# mw_itb_half_v1_7_2.net
KiCad netlist of a schematic drawn in EAGLE
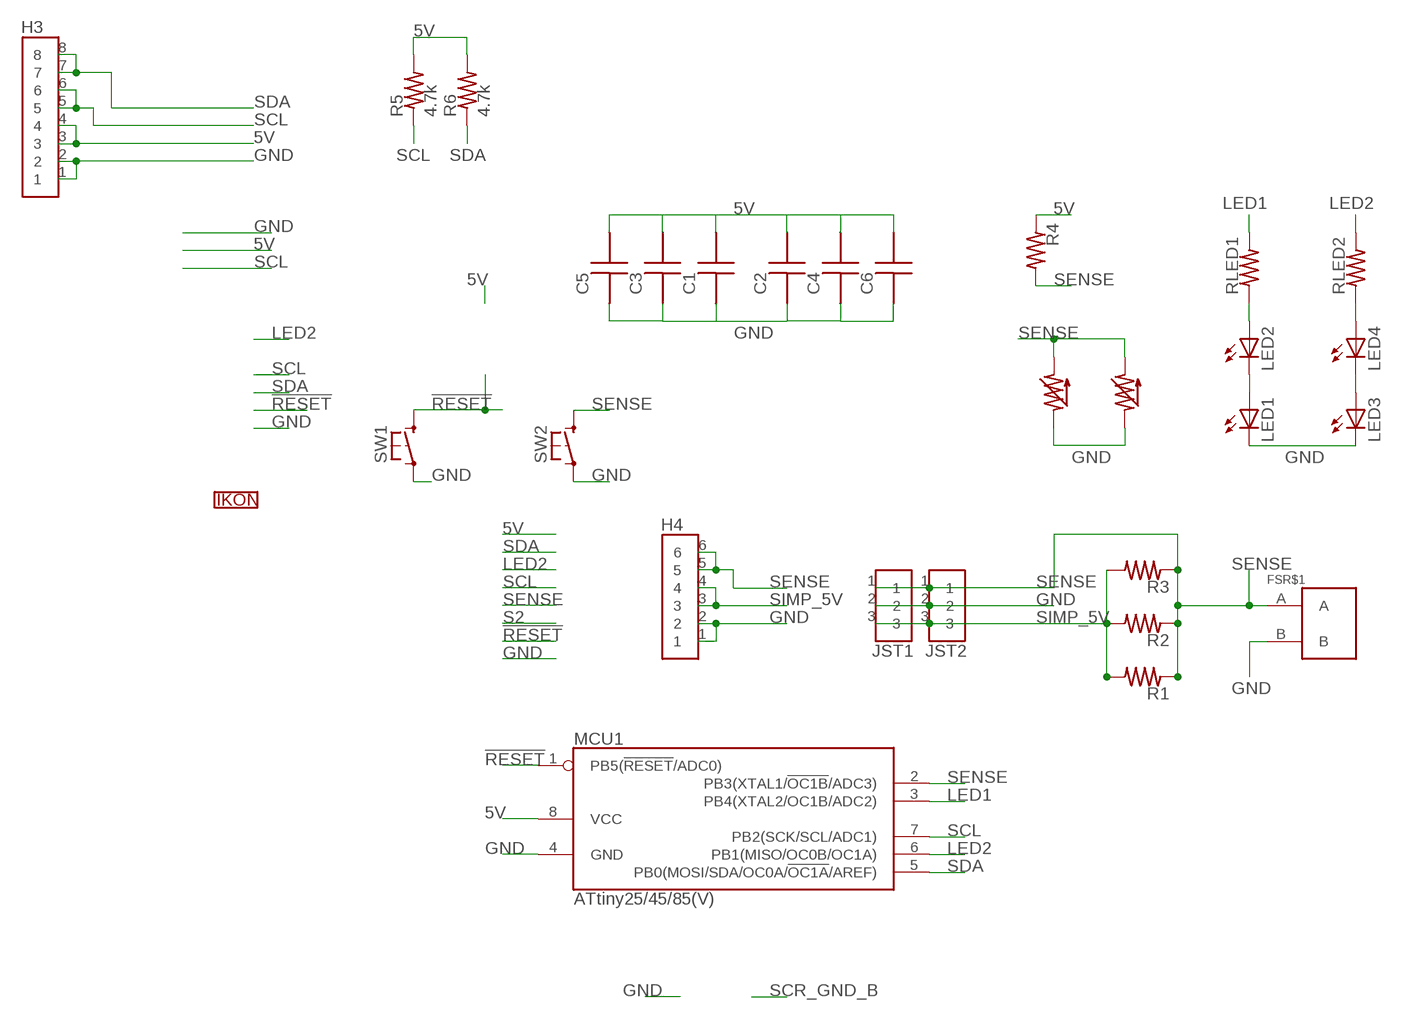
[diagram p0: schematic, sheet 1]

(export (version "E")
  (design (tool "Eeschema 10.0.6"))
  (components
    (comp (ref "C1")
      (value "CAPACITOR1206")
      (footprint "eagle-import:1206_YAGEO")
      (libsource (lib "eagle-import") (part "CAPACITOR1206"))
    )
    (comp (ref "C2")
      (value "CAPACITOR1206")
      (footprint "eagle-import:1206_YAGEO")
      (libsource (lib "eagle-import") (part "CAPACITOR1206"))
    )
    (comp (ref "C3")
      (value "CAPACITOR0805")
      (footprint "eagle-import:0805_YAGEO")
      (libsource (lib "eagle-import") (part "CAPACITOR0805"))
    )
    (comp (ref "C4")
      (value "CAPACITOR0805")
      (footprint "eagle-import:0805_YAGEO")
      (libsource (lib "eagle-import") (part "CAPACITOR0805"))
    )
    (comp (ref "C5")
      (value "CAPACITOR0603")
      (footprint "eagle-import:0603_YAGEO")
      (libsource (lib "eagle-import") (part "CAPACITOR0603"))
    )
    (comp (ref "C6")
      (value "CAPACITOR0603")
      (footprint "eagle-import:0603_YAGEO")
      (libsource (lib "eagle-import") (part "CAPACITOR0603"))
    )
    (comp (ref "FSR$1")
      (value "FSR_PAD88X44_P2B")
      (footprint "eagle-import:FSR_PAD_88X44_P2B")
      (libsource (lib "eagle-import") (part "FSR_PAD88X44_P2B"))
    )
    (comp (ref "H3")
      (value "HEADER_8P-0.1\"_2X4-SMD-SULLINS")
      (footprint "eagle-import:HEADER-0.1__2X4-SMD-SULLINS")
      (libsource (lib "eagle-import") (part "HEADER_8P-0.1{dblquote}_2X4-SMD-SULLINS"))
    )
    (comp (ref "H4")
      (value "HEADER_6P-0.1\"_2X3-SMD-SULLINS")
      (footprint "eagle-import:HEADER-0.1__2X3-SMD-SULLINS")
      (libsource (lib "eagle-import") (part "HEADER_6P-0.1{dblquote}_2X3-SMD-SULLINS"))
    )
    (comp (ref "JST1")
      (value "JST-3-PH-SMD-TOP")
      (footprint "eagle-import:JST_PH_SMD_3_TOP")
      (libsource (lib "eagle-import") (part "JST-3-PH-SMD-TOP"))
    )
    (comp (ref "JST2")
      (value "JST-3-PH-SMD-TOP")
      (footprint "eagle-import:JST_PH_SMD_3_TOP")
      (libsource (lib "eagle-import") (part "JST-3-PH-SMD-TOP"))
    )
    (comp (ref "LED1")
      (value "LED-ZBEND_RM")
      (footprint "eagle-import:Z-BEND_RM")
      (libsource (lib "eagle-import") (part "LED-ZBEND_RM"))
    )
    (comp (ref "LED2")
      (value "LED-ZBEND_RM")
      (footprint "eagle-import:Z-BEND_RM")
      (libsource (lib "eagle-import") (part "LED-ZBEND_RM"))
    )
    (comp (ref "LED3")
      (value "LED-ZBEND_RM")
      (footprint "eagle-import:Z-BEND_RM")
      (libsource (lib "eagle-import") (part "LED-ZBEND_RM"))
    )
    (comp (ref "LED4")
      (value "LED-ZBEND_RM")
      (footprint "eagle-import:Z-BEND_RM")
      (libsource (lib "eagle-import") (part "LED-ZBEND_RM"))
    )
    (comp (ref "MCU1")
      (value "ATMEL_ATTINY25/45/85(V)-SOIC_DUAL")
      (footprint "eagle-import:SOIC-8_DUAL")
      (libsource (lib "eagle-import") (part "ATMEL_ATTINY25/45/85(V)-SOIC_DUAL"))
    )
    (comp (ref "R1")
      (value "RESISTOR1206")
      (footprint "eagle-import:1206_YAGEO")
      (libsource (lib "eagle-import") (part "RESISTOR1206"))
    )
    (comp (ref "R2")
      (value "RESISTOR0805")
      (footprint "eagle-import:0805_YAGEO")
      (libsource (lib "eagle-import") (part "RESISTOR0805"))
    )
    (comp (ref "R3")
      (value "RESISTOR0603")
      (footprint "eagle-import:0603_YAGEO")
      (libsource (lib "eagle-import") (part "RESISTOR0603"))
    )
    (comp (ref "R4")
      (value "RESISTOR0603")
      (footprint "eagle-import:0603_YAGEO")
      (libsource (lib "eagle-import") (part "RESISTOR0603"))
    )
    (comp (ref "R5")
      (value "4.7k")
      (footprint "eagle-import:0603_YAGEO")
      (libsource (lib "eagle-import") (part "RESISTOR0603"))
    )
    (comp (ref "R6")
      (value "4.7k")
      (footprint "eagle-import:0603_YAGEO")
      (libsource (lib "eagle-import") (part "RESISTOR0603"))
    )
    (comp (ref "RLED1")
      (value "RESISTOR0603")
      (footprint "eagle-import:0603_YAGEO")
      (libsource (lib "eagle-import") (part "RESISTOR0603"))
    )
    (comp (ref "RLED2")
      (value "RESISTOR0603")
      (footprint "eagle-import:0603_YAGEO")
      (libsource (lib "eagle-import") (part "RESISTOR0603"))
    )
    (comp (ref "SW1")
      (value "SWITCH_SPST-KMT0")
      (footprint "eagle-import:KMT0")
      (libsource (lib "eagle-import") (part "SWITCH_SPST-KMT0"))
    )
    (comp (ref "SW2")
      (value "SWITCH_SPST-KMT0")
      (footprint "eagle-import:KMT0")
      (libsource (lib "eagle-import") (part "SWITCH_SPST-KMT0"))
    )
    (comp (ref "U$5")
      (value "FSR_PLACE")
      (footprint "eagle-import:FSR_1.5[IN]_SQR")
      (libsource (lib "eagle-import") (part "FSR_PLACE1.5{dblquote}SQR"))
    )
    (comp (ref "U$6")
      (value "FSR_PLACE")
      (footprint "eagle-import:FSR_1.5[IN]_SQR")
      (libsource (lib "eagle-import") (part "FSR_PLACE1.5{dblquote}SQR"))
    )
    (comp (ref "U$9")
      (value "FSR_PINS")
      (footprint "eagle-import:FSR_0.1_-PITCH_PADS-0.05_X0.5_")
      (libsource (lib "eagle-import") (part "FSR_PINSJUMBO_SMD"))
    )
    (comp (ref "U$10")
      (value "FSR_PINS")
      (footprint "eagle-import:FSR_0.1_-PITCH_PADS-0.05_X0.5_")
      (libsource (lib "eagle-import") (part "FSR_PINSJUMBO_SMD"))
    )
    (comp (ref "U$11")
      (value "IKONLEARNING-20MIL")
      (footprint "eagle-import:IKON_LEARNING_20MIL")
      (libsource (lib "eagle-import") (part "IKONLEARNING-20MIL"))
    )
  )
  (nets
    (net (code "1") (name "/5V") (class "Default")
      (node (ref "C1") (pin "1") (pinfunction "P$1_1") (pintype "passive"))
      (node (ref "C2") (pin "1") (pinfunction "P$1_1") (pintype "passive"))
      (node (ref "C3") (pin "1") (pinfunction "P$1_1") (pintype "passive"))
      (node (ref "C4") (pin "1") (pinfunction "P$1_1") (pintype "passive"))
      (node (ref "C5") (pin "1") (pinfunction "P$1_1") (pintype "passive"))
      (node (ref "C6") (pin "1") (pinfunction "P$1_1") (pintype "passive"))
      (node (ref "H3") (pin "3") (pinfunction "3_3") (pintype "bidirectional"))
      (node (ref "H3") (pin "4") (pinfunction "4_4") (pintype "bidirectional"))
      (node (ref "MCU1") (pin "8") (pinfunction "VCC_8") (pintype "bidirectional"))
      (node (ref "R4") (pin "1") (pinfunction "1_1") (pintype "passive"))
      (node (ref "R5") (pin "2") (pinfunction "2_2") (pintype "passive"))
      (node (ref "R6") (pin "2") (pinfunction "2_2") (pintype "passive"))
    )
    (net (code "2") (name "/GND") (class "Default")
      (node (ref "C1") (pin "2") (pinfunction "P$2_2") (pintype "passive"))
      (node (ref "C2") (pin "2") (pinfunction "P$2_2") (pintype "passive"))
      (node (ref "C3") (pin "2") (pinfunction "P$2_2") (pintype "passive"))
      (node (ref "C4") (pin "2") (pinfunction "P$2_2") (pintype "passive"))
      (node (ref "C5") (pin "2") (pinfunction "P$2_2") (pintype "passive"))
      (node (ref "C6") (pin "2") (pinfunction "P$2_2") (pintype "passive"))
      (node (ref "FSR$1") (pin "B") (pinfunction "B_B") (pintype "bidirectional"))
      (node (ref "H3") (pin "1") (pinfunction "1_1") (pintype "bidirectional"))
      (node (ref "H3") (pin "2") (pinfunction "2_2") (pintype "bidirectional"))
      (node (ref "H4") (pin "1") (pinfunction "1_1") (pintype "bidirectional"))
      (node (ref "H4") (pin "2") (pinfunction "2_2") (pintype "bidirectional"))
      (node (ref "JST1") (pin "2") (pinfunction "2_2") (pintype "bidirectional"))
      (node (ref "JST2") (pin "2") (pinfunction "2_2") (pintype "bidirectional"))
      (node (ref "LED1") (pin "K") (pinfunction "C_K") (pintype "passive"))
      (node (ref "LED3") (pin "K") (pinfunction "C_K") (pintype "passive"))
      (node (ref "MCU1") (pin "4") (pinfunction "GND_4") (pintype "bidirectional"))
      (node (ref "SW1") (pin "2@1") (pinfunction "2_2@1") (pintype "passive"))
      (node (ref "SW1") (pin "2@2") (pinfunction "2_2@2") (pintype "passive"))
      (node (ref "SW2") (pin "2@1") (pinfunction "2_2@1") (pintype "passive"))
      (node (ref "SW2") (pin "2@2") (pinfunction "2_2@2") (pintype "passive"))
      (node (ref "U$10") (pin "P$1") (pinfunction "P$1_P$1") (pintype "bidirectional"))
      (node (ref "U$9") (pin "P$2") (pinfunction "P$2_P$2") (pintype "bidirectional"))
    )
    (net (code "3") (name "/LED1") (class "Default")
      (node (ref "MCU1") (pin "3") (pinfunction "PB4(XTAL2/OC1B/ADC2)_3") (pintype "bidirectional"))
      (node (ref "RLED1") (pin "2") (pinfunction "2_2") (pintype "passive"))
    )
    (net (code "4") (name "/LED2") (class "Default")
      (node (ref "MCU1") (pin "6") (pinfunction "PB1(MISO/OC0B/OC1A)_6") (pintype "bidirectional"))
      (node (ref "RLED2") (pin "2") (pinfunction "2_2") (pintype "passive"))
    )
    (net (code "6") (name "/SCL") (class "Default")
      (node (ref "H3") (pin "5") (pinfunction "5_5") (pintype "bidirectional"))
      (node (ref "H3") (pin "6") (pinfunction "6_6") (pintype "bidirectional"))
      (node (ref "MCU1") (pin "7") (pinfunction "PB2(SCK/SCL/ADC1)_7") (pintype "bidirectional"))
      (node (ref "R5") (pin "1") (pinfunction "1_1") (pintype "passive"))
    )
    (net (code "8") (name "/SDA") (class "Default")
      (node (ref "H3") (pin "7") (pinfunction "7_7") (pintype "bidirectional"))
      (node (ref "H3") (pin "8") (pinfunction "8_8") (pintype "bidirectional"))
      (node (ref "MCU1") (pin "5") (pinfunction "PB0(MOSI/SDA/OC0A/~{OC1A}/AREF)_5") (pintype "bidirectional"))
      (node (ref "R6") (pin "1") (pinfunction "1_1") (pintype "passive"))
    )
    (net (code "9") (name "/SENSE") (class "Default")
      (node (ref "FSR$1") (pin "A") (pinfunction "A_A") (pintype "bidirectional"))
      (node (ref "H4") (pin "5") (pinfunction "5_5") (pintype "bidirectional"))
      (node (ref "H4") (pin "6") (pinfunction "6_6") (pintype "bidirectional"))
      (node (ref "JST1") (pin "1") (pinfunction "1_1") (pintype "bidirectional"))
      (node (ref "JST2") (pin "1") (pinfunction "1_1") (pintype "bidirectional"))
      (node (ref "MCU1") (pin "2") (pinfunction "PB3(XTAL1/~{OC1B}/ADC3)_2") (pintype "bidirectional"))
      (node (ref "R1") (pin "1") (pinfunction "1_1") (pintype "passive"))
      (node (ref "R2") (pin "1") (pinfunction "1_1") (pintype "passive"))
      (node (ref "R3") (pin "1") (pinfunction "1_1") (pintype "passive"))
      (node (ref "R4") (pin "2") (pinfunction "2_2") (pintype "passive"))
      (node (ref "SW2") (pin "1@1") (pinfunction "1_1@1") (pintype "passive"))
      (node (ref "SW2") (pin "1@2") (pinfunction "1_1@2") (pintype "passive"))
      (node (ref "U$10") (pin "P$2") (pinfunction "P$2_P$2") (pintype "bidirectional"))
      (node (ref "U$9") (pin "P$1") (pinfunction "P$1_P$1") (pintype "bidirectional"))
    )
    (net (code "10") (name "/SIMP_5V") (class "Default")
      (node (ref "H4") (pin "3") (pinfunction "3_3") (pintype "bidirectional"))
      (node (ref "H4") (pin "4") (pinfunction "4_4") (pintype "bidirectional"))
      (node (ref "JST1") (pin "3") (pinfunction "3_3") (pintype "bidirectional"))
      (node (ref "JST2") (pin "3") (pinfunction "3_3") (pintype "bidirectional"))
      (node (ref "R1") (pin "2") (pinfunction "2_2") (pintype "passive"))
      (node (ref "R2") (pin "2") (pinfunction "2_2") (pintype "passive"))
      (node (ref "R3") (pin "2") (pinfunction "2_2") (pintype "passive"))
    )
    (net (code "11") (name "/~{RESET}") (class "Default")
      (node (ref "MCU1") (pin "1") (pinfunction "PB5(~{RESET}/ADC0)_1") (pintype "bidirectional"))
      (node (ref "SW1") (pin "1@1") (pinfunction "1_1@1") (pintype "passive"))
      (node (ref "SW1") (pin "1@2") (pinfunction "1_1@2") (pintype "passive"))
    )
    (net (code "12") (name "Net-(LED2-C)") (class "Default")
      (node (ref "LED1") (pin "A") (pinfunction "A_A") (pintype "passive"))
      (node (ref "LED2") (pin "K") (pinfunction "C_K") (pintype "passive"))
    )
    (net (code "13") (name "Net-(LED2-PadA)") (class "Default")
      (node (ref "LED2") (pin "A") (pinfunction "A_A") (pintype "passive"))
      (node (ref "RLED1") (pin "1") (pinfunction "1_1") (pintype "passive"))
    )
    (net (code "14") (name "Net-(LED4-C)") (class "Default")
      (node (ref "LED3") (pin "A") (pinfunction "A_A") (pintype "passive"))
      (node (ref "LED4") (pin "K") (pinfunction "C_K") (pintype "passive"))
    )
    (net (code "15") (name "Net-(LED4-PadA)") (class "Default")
      (node (ref "LED4") (pin "A") (pinfunction "A_A") (pintype "passive"))
      (node (ref "RLED2") (pin "1") (pinfunction "1_1") (pintype "passive"))
    )
  )
)
